# Analogue.net
KiCad netlist of a schematic drawn in Altium Designer
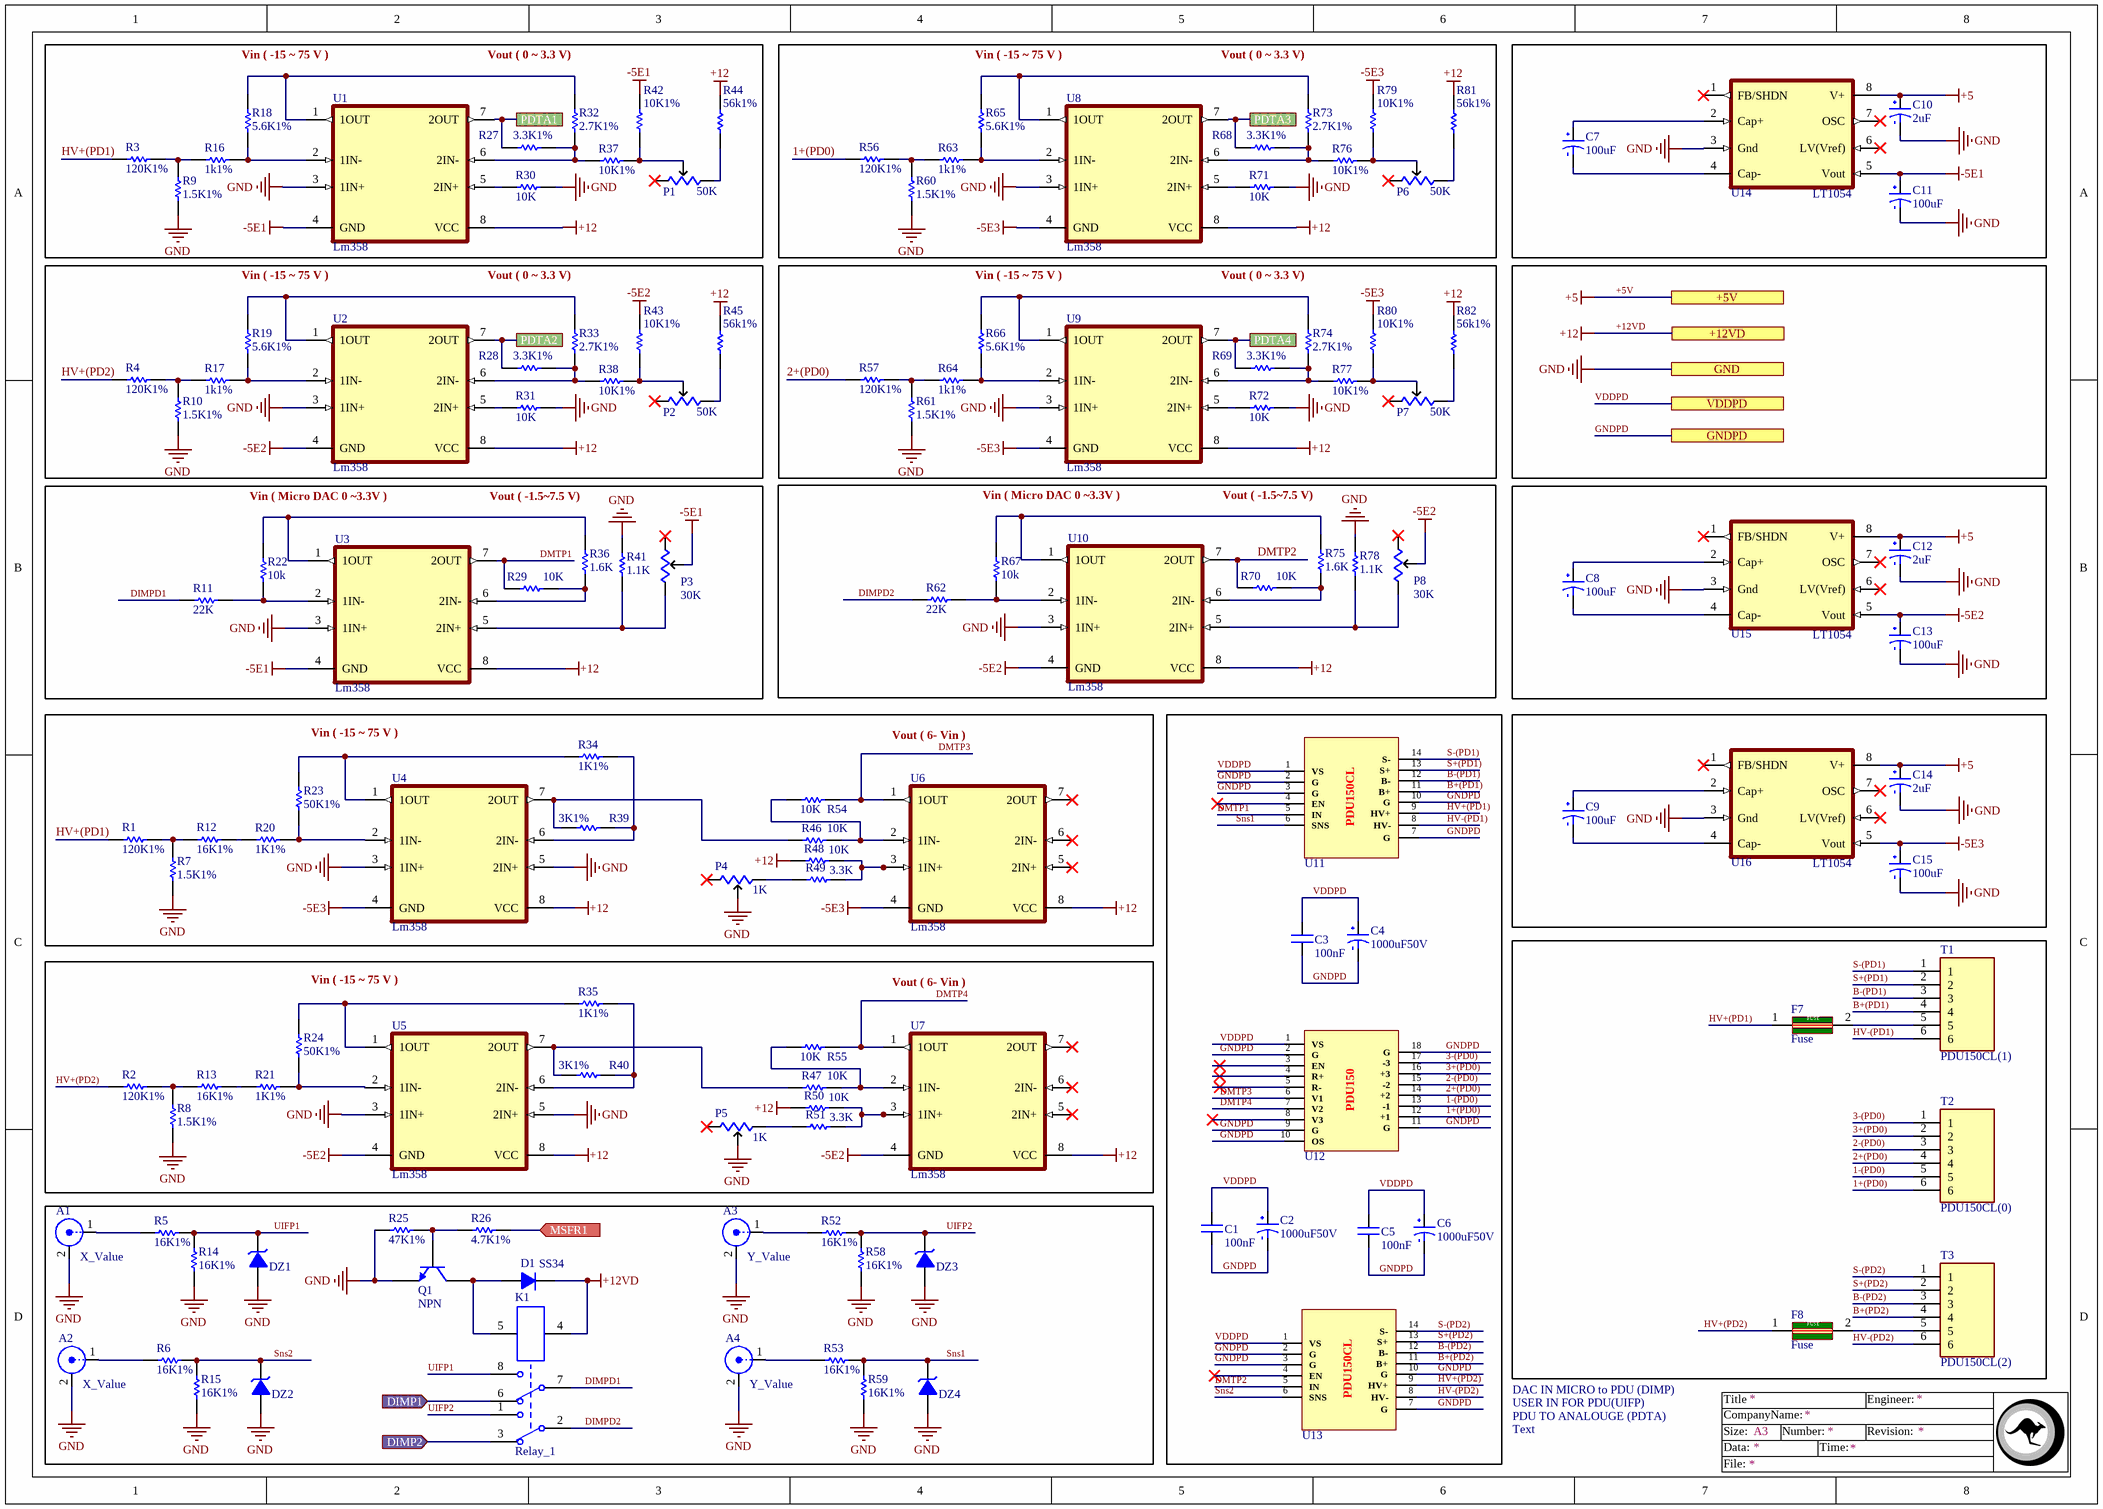
[diagram p0: Analogue.SchDoc]

(export (version "E")
  (design (tool "Eeschema 10.0.6"))
  (components
    (comp (ref "A1")
      (value "X_Value")
      (footprint "SMA - R")
      (description "Antena MLF")
      (libsource (lib "PMLIB2020-V3") (part "ANTENA"))
    )
    (comp (ref "A2")
      (value "X_Value")
      (footprint "SMA - R")
      (description "Antena MLF")
      (libsource (lib "PMLIB2020-V3") (part "ANTENA"))
    )
    (comp (ref "A3")
      (value "Y_Value")
      (footprint "SMA - R")
      (description "Antena MLF")
      (libsource (lib "PMLIB2020-V3") (part "ANTENA"))
    )
    (comp (ref "A4")
      (value "Y_Value")
      (footprint "SMA - R")
      (description "Antena MLF")
      (libsource (lib "PMLIB2020-V3") (part "ANTENA"))
    )
    (comp (ref "C1")
      (value "100nF")
      (footprint "Cap0805")
      (description "Surface mount Capacitor")
      (libsource (lib "PMLIB2020-V3") (part "Cap"))
    )
    (comp (ref "C2")
      (value "1000uF50V")
      (footprint "Cap_5mm")
      (description "Polarity")
      (libsource (lib "PMLIB2020-V3") (part "Cap_P"))
    )
    (comp (ref "C3")
      (value "100nF")
      (footprint "Cap0805")
      (description "Surface mount Capacitor")
      (libsource (lib "PMLIB2020-V3") (part "Cap"))
    )
    (comp (ref "C4")
      (value "1000uF50V")
      (footprint "Cap_5mm")
      (description "Polarity")
      (libsource (lib "PMLIB2020-V3") (part "Cap_P"))
    )
    (comp (ref "C5")
      (value "100nF")
      (footprint "Cap0805")
      (description "Surface mount Capacitor")
      (libsource (lib "PMLIB2020-V3") (part "Cap"))
    )
    (comp (ref "C6")
      (value "1000uF50V")
      (footprint "Cap_5mm")
      (description "Polarity")
      (libsource (lib "PMLIB2020-V3") (part "Cap_P"))
    )
    (comp (ref "C7")
      (value "100uF")
      (footprint "CAPMOL_D")
      (description "Polarity")
      (libsource (lib "PMLIB2020-V3") (part "Cap_P"))
    )
    (comp (ref "C8")
      (value "100uF")
      (footprint "CAPMOL_D")
      (description "Polarity")
      (libsource (lib "PMLIB2020-V3") (part "Cap_P"))
    )
    (comp (ref "C9")
      (value "100uF")
      (footprint "CAPMOL_D")
      (description "Polarity")
      (libsource (lib "PMLIB2020-V3") (part "Cap_P"))
    )
    (comp (ref "C10")
      (value "2uF")
      (footprint "CAPMOL_B")
      (description "Polarity")
      (libsource (lib "PMLIB2020-V3") (part "Cap_P"))
    )
    (comp (ref "C11")
      (value "100uF")
      (footprint "CAPMOL_D")
      (description "Polarity")
      (libsource (lib "PMLIB2020-V3") (part "Cap_P"))
    )
    (comp (ref "C12")
      (value "2uF")
      (footprint "CAPMOL_B")
      (description "Polarity")
      (libsource (lib "PMLIB2020-V3") (part "Cap_P"))
    )
    (comp (ref "C13")
      (value "100uF")
      (footprint "CAPMOL_D")
      (description "Polarity")
      (libsource (lib "PMLIB2020-V3") (part "Cap_P"))
    )
    (comp (ref "C14")
      (value "2uF")
      (footprint "CAPMOL_B")
      (description "Polarity")
      (libsource (lib "PMLIB2020-V3") (part "Cap_P"))
    )
    (comp (ref "C15")
      (value "100uF")
      (footprint "CAPMOL_D")
      (description "Polarity")
      (libsource (lib "PMLIB2020-V3") (part "Cap_P"))
    )
    (comp (ref "D1")
      (value "SS34")
      (footprint "Diod-1A-SMD")
      (description "Diode")
      (libsource (lib "PMLIB2020-V3") (part "Diode"))
    )
    (comp (ref "DZ1")
      (value "Diode Zener")
      (footprint "LL4148")
      (libsource (lib "PMLIB2020-V3") (part "Diode Zener"))
    )
    (comp (ref "DZ2")
      (value "Diode Zener")
      (footprint "LL4148")
      (libsource (lib "PMLIB2020-V3") (part "Diode Zener"))
    )
    (comp (ref "DZ3")
      (value "Diode Zener")
      (footprint "LL4148")
      (libsource (lib "PMLIB2020-V3") (part "Diode Zener"))
    )
    (comp (ref "DZ4")
      (value "Diode Zener")
      (footprint "LL4148")
      (libsource (lib "PMLIB2020-V3") (part "Diode Zener"))
    )
    (comp (ref "F7") (value "Fuse") (footprint "1206") (libsource (lib "PMLIB2020-V3") (part "Fuse")))
    (comp (ref "F8") (value "Fuse") (footprint "1206") (libsource (lib "PMLIB2020-V3") (part "Fuse")))
    (comp (ref "K1")
      (value "Relay_1")
      (footprint "Relay_1")
      (description "Relay")
      (libsource (lib "PMLIB2020-V3") (part "Relay_1"))
    )
    (comp (ref "P1")
      (value "50K")
      (footprint "Multi_tern")
      (description "Potentiometer")
      (libsource (lib "PMLIB2020-V3") (part "POT"))
    )
    (comp (ref "P2")
      (value "50K")
      (footprint "Multi_tern")
      (description "Potentiometer")
      (libsource (lib "PMLIB2020-V3") (part "POT"))
    )
    (comp (ref "P3")
      (value "30K")
      (footprint "Multi_tern")
      (description "Potentiometer")
      (libsource (lib "PMLIB2020-V3") (part "POT"))
    )
    (comp (ref "P4")
      (value "1K")
      (footprint "Multi_tern")
      (description "Potentiometer")
      (libsource (lib "PMLIB2020-V3") (part "POT"))
    )
    (comp (ref "P5")
      (value "1K")
      (footprint "Multi_tern")
      (description "Potentiometer")
      (libsource (lib "PMLIB2020-V3") (part "POT"))
    )
    (comp (ref "P6")
      (value "50K")
      (footprint "Multi_tern")
      (description "Potentiometer")
      (libsource (lib "PMLIB2020-V3") (part "POT"))
    )
    (comp (ref "P7")
      (value "50K")
      (footprint "Multi_tern")
      (description "Potentiometer")
      (libsource (lib "PMLIB2020-V3") (part "POT"))
    )
    (comp (ref "P8")
      (value "30K")
      (footprint "Multi_tern")
      (description "Potentiometer")
      (libsource (lib "PMLIB2020-V3") (part "POT"))
    )
    (comp (ref "Q1")
      (value "NPN")
      (footprint "SOT23_BEC_N")
      (description "NPN Bipolar Transistor")
      (fields (field (name "PUBLISHER") "Altium Limited"))
      (libsource (lib "PMLIB2020-V3") (part "NPN"))
    )
    (comp (ref "R1")
      (value "120K1%")
      (footprint "R0805")
      (description "30K")
      (libsource (lib "PMLIB2020-V3") (part "Resistor"))
    )
    (comp (ref "R2")
      (value "120K1%")
      (footprint "R0805")
      (description "30K")
      (libsource (lib "PMLIB2020-V3") (part "Resistor"))
    )
    (comp (ref "R3")
      (value "120K1%")
      (footprint "R0805")
      (description "30K")
      (libsource (lib "PMLIB2020-V3") (part "Resistor"))
    )
    (comp (ref "R4")
      (value "120K1%")
      (footprint "R0805")
      (description "30K")
      (libsource (lib "PMLIB2020-V3") (part "Resistor"))
    )
    (comp (ref "R5")
      (value "16K1%")
      (footprint "R0805")
      (description "30K")
      (libsource (lib "PMLIB2020-V3") (part "Resistor"))
    )
    (comp (ref "R6")
      (value "16K1%")
      (footprint "R0805")
      (description "30K")
      (libsource (lib "PMLIB2020-V3") (part "Resistor"))
    )
    (comp (ref "R7")
      (value "1.5K1%")
      (footprint "R0805")
      (description "30K")
      (libsource (lib "PMLIB2020-V3") (part "Resistor"))
    )
    (comp (ref "R8")
      (value "1.5K1%")
      (footprint "R0805")
      (description "30K")
      (libsource (lib "PMLIB2020-V3") (part "Resistor"))
    )
    (comp (ref "R9")
      (value "1.5K1%")
      (footprint "R0805")
      (description "30K")
      (libsource (lib "PMLIB2020-V3") (part "Resistor"))
    )
    (comp (ref "R10")
      (value "1.5K1%")
      (footprint "R0805")
      (description "30K")
      (libsource (lib "PMLIB2020-V3") (part "Resistor"))
    )
    (comp (ref "R11")
      (value "22K")
      (footprint "R0805")
      (description "30K")
      (libsource (lib "PMLIB2020-V3") (part "Resistor"))
    )
    (comp (ref "R12")
      (value "16K1%")
      (footprint "R0805")
      (description "30K")
      (libsource (lib "PMLIB2020-V3") (part "Resistor"))
    )
    (comp (ref "R13")
      (value "16K1%")
      (footprint "R0805")
      (description "30K")
      (libsource (lib "PMLIB2020-V3") (part "Resistor"))
    )
    (comp (ref "R14")
      (value "16K1%")
      (footprint "R0805")
      (description "30K")
      (libsource (lib "PMLIB2020-V3") (part "Resistor"))
    )
    (comp (ref "R15")
      (value "16K1%")
      (footprint "R0805")
      (description "30K")
      (libsource (lib "PMLIB2020-V3") (part "Resistor"))
    )
    (comp (ref "R16")
      (value "1k1%")
      (footprint "R0805")
      (description "30K")
      (libsource (lib "PMLIB2020-V3") (part "Resistor"))
    )
    (comp (ref "R17")
      (value "1k1%")
      (footprint "R0805")
      (description "30K")
      (libsource (lib "PMLIB2020-V3") (part "Resistor"))
    )
    (comp (ref "R18")
      (value "5.6K1%")
      (footprint "R0805")
      (description "Resistor")
      (libsource (lib "PMLIB2020-V3") (part "Resistor"))
    )
    (comp (ref "R19")
      (value "5.6K1%")
      (footprint "R0805")
      (description "Resistor")
      (libsource (lib "PMLIB2020-V3") (part "Resistor"))
    )
    (comp (ref "R20")
      (value "1K1%")
      (footprint "R0805")
      (description "30K")
      (libsource (lib "PMLIB2020-V3") (part "Resistor"))
    )
    (comp (ref "R21")
      (value "1K1%")
      (footprint "R0805")
      (description "30K")
      (libsource (lib "PMLIB2020-V3") (part "Resistor"))
    )
    (comp (ref "R22")
      (value "10k")
      (footprint "R0805")
      (description "Resistor")
      (libsource (lib "PMLIB2020-V3") (part "Resistor"))
    )
    (comp (ref "R23")
      (value "50K1%")
      (footprint "R0805")
      (description "Resistor")
      (libsource (lib "PMLIB2020-V3") (part "Resistor"))
    )
    (comp (ref "R24")
      (value "50K1%")
      (footprint "R0805")
      (description "Resistor")
      (libsource (lib "PMLIB2020-V3") (part "Resistor"))
    )
    (comp (ref "R25")
      (value "47K1%")
      (footprint "R0805")
      (description "30K")
      (libsource (lib "PMLIB2020-V3") (part "Resistor"))
    )
    (comp (ref "R26")
      (value "4.7K1%")
      (footprint "R0805")
      (description "30K")
      (libsource (lib "PMLIB2020-V3") (part "Resistor"))
    )
    (comp (ref "R27")
      (value "3.3K1%")
      (footprint "R0805")
      (description "Resistor")
      (libsource (lib "PMLIB2020-V3") (part "Resistor"))
    )
    (comp (ref "R28")
      (value "3.3K1%")
      (footprint "R0805")
      (description "Resistor")
      (libsource (lib "PMLIB2020-V3") (part "Resistor"))
    )
    (comp (ref "R29")
      (value "10K")
      (footprint "R0805")
      (description "Resistor")
      (libsource (lib "PMLIB2020-V3") (part "Resistor"))
    )
    (comp (ref "R30")
      (value "10K")
      (footprint "R0805")
      (description "Resistor")
      (libsource (lib "PMLIB2020-V3") (part "Resistor"))
    )
    (comp (ref "R31")
      (value "10K")
      (footprint "R0805")
      (description "Resistor")
      (libsource (lib "PMLIB2020-V3") (part "Resistor"))
    )
    (comp (ref "R32")
      (value "2.7K1%")
      (footprint "R0805")
      (description "Resistor")
      (libsource (lib "PMLIB2020-V3") (part "Resistor"))
    )
    (comp (ref "R33")
      (value "2.7K1%")
      (footprint "R0805")
      (description "Resistor")
      (libsource (lib "PMLIB2020-V3") (part "Resistor"))
    )
    (comp (ref "R34")
      (value "1K1%")
      (footprint "R0805")
      (description "Resistor")
      (libsource (lib "PMLIB2020-V3") (part "Resistor"))
    )
    (comp (ref "R35")
      (value "1K1%")
      (footprint "R0805")
      (description "Resistor")
      (libsource (lib "PMLIB2020-V3") (part "Resistor"))
    )
    (comp (ref "R36")
      (value "1.6K")
      (footprint "R0805")
      (description "Resistor")
      (libsource (lib "PMLIB2020-V3") (part "Resistor"))
    )
    (comp (ref "R37")
      (value "10K1%")
      (footprint "R0805")
      (description "Resistor")
      (libsource (lib "PMLIB2020-V3") (part "Resistor"))
    )
    (comp (ref "R38")
      (value "10K1%")
      (footprint "R0805")
      (description "Resistor")
      (libsource (lib "PMLIB2020-V3") (part "Resistor"))
    )
    (comp (ref "R39")
      (value "3K1%")
      (footprint "R0805")
      (description "Resistor")
      (libsource (lib "PMLIB2020-V3") (part "Resistor"))
    )
    (comp (ref "R40")
      (value "3K1%")
      (footprint "R0805")
      (description "Resistor")
      (libsource (lib "PMLIB2020-V3") (part "Resistor"))
    )
    (comp (ref "R41")
      (value "1.1K")
      (footprint "R0805")
      (description "Resistor")
      (libsource (lib "PMLIB2020-V3") (part "Resistor"))
    )
    (comp (ref "R42")
      (value "10K1%")
      (footprint "R0805")
      (description "Resistor")
      (libsource (lib "PMLIB2020-V3") (part "Resistor"))
    )
    (comp (ref "R43")
      (value "10K1%")
      (footprint "R0805")
      (description "Resistor")
      (libsource (lib "PMLIB2020-V3") (part "Resistor"))
    )
    (comp (ref "R44")
      (value "56k1%")
      (footprint "R0805")
      (description "Resistor")
      (libsource (lib "PMLIB2020-V3") (part "Resistor"))
    )
    (comp (ref "R45")
      (value "56k1%")
      (footprint "R0805")
      (description "Resistor")
      (libsource (lib "PMLIB2020-V3") (part "Resistor"))
    )
    (comp (ref "R46")
      (value "10K")
      (footprint "R0805")
      (description "Resistor")
      (libsource (lib "PMLIB2020-V3") (part "Resistor"))
    )
    (comp (ref "R47")
      (value "10K")
      (footprint "R0805")
      (description "Resistor")
      (libsource (lib "PMLIB2020-V3") (part "Resistor"))
    )
    (comp (ref "R48")
      (value "10K")
      (footprint "R0805")
      (description "Resistor")
      (libsource (lib "PMLIB2020-V3") (part "Resistor"))
    )
    (comp (ref "R49")
      (value "3.3K")
      (footprint "R0805")
      (description "Resistor")
      (libsource (lib "PMLIB2020-V3") (part "Resistor"))
    )
    (comp (ref "R50")
      (value "10K")
      (footprint "R0805")
      (description "Resistor")
      (libsource (lib "PMLIB2020-V3") (part "Resistor"))
    )
    (comp (ref "R51")
      (value "3.3K")
      (footprint "R0805")
      (description "Resistor")
      (libsource (lib "PMLIB2020-V3") (part "Resistor"))
    )
    (comp (ref "R52")
      (value "16K1%")
      (footprint "R0805")
      (description "30K")
      (libsource (lib "PMLIB2020-V3") (part "Resistor"))
    )
    (comp (ref "R53")
      (value "16K1%")
      (footprint "R0805")
      (description "30K")
      (libsource (lib "PMLIB2020-V3") (part "Resistor"))
    )
    (comp (ref "R54")
      (value "10K")
      (footprint "R0805")
      (description "Resistor")
      (libsource (lib "PMLIB2020-V3") (part "Resistor"))
    )
    (comp (ref "R55")
      (value "10K")
      (footprint "R0805")
      (description "Resistor")
      (libsource (lib "PMLIB2020-V3") (part "Resistor"))
    )
    (comp (ref "R56")
      (value "120K1%")
      (footprint "R0805")
      (description "30K")
      (libsource (lib "PMLIB2020-V3") (part "Resistor"))
    )
    (comp (ref "R57")
      (value "120K1%")
      (footprint "R0805")
      (description "30K")
      (libsource (lib "PMLIB2020-V3") (part "Resistor"))
    )
    (comp (ref "R58")
      (value "16K1%")
      (footprint "R0805")
      (description "30K")
      (libsource (lib "PMLIB2020-V3") (part "Resistor"))
    )
    (comp (ref "R59")
      (value "16K1%")
      (footprint "R0805")
      (description "30K")
      (libsource (lib "PMLIB2020-V3") (part "Resistor"))
    )
    (comp (ref "R60")
      (value "1.5K1%")
      (footprint "R0805")
      (description "30K")
      (libsource (lib "PMLIB2020-V3") (part "Resistor"))
    )
    (comp (ref "R61")
      (value "1.5K1%")
      (footprint "R0805")
      (description "30K")
      (libsource (lib "PMLIB2020-V3") (part "Resistor"))
    )
    (comp (ref "R62")
      (value "22K")
      (footprint "R0805")
      (description "30K")
      (libsource (lib "PMLIB2020-V3") (part "Resistor"))
    )
    (comp (ref "R63")
      (value "1k1%")
      (footprint "R0805")
      (description "30K")
      (libsource (lib "PMLIB2020-V3") (part "Resistor"))
    )
    (comp (ref "R64")
      (value "1k1%")
      (footprint "R0805")
      (description "30K")
      (libsource (lib "PMLIB2020-V3") (part "Resistor"))
    )
    (comp (ref "R65")
      (value "5.6K1%")
      (footprint "R0805")
      (description "Resistor")
      (libsource (lib "PMLIB2020-V3") (part "Resistor"))
    )
    (comp (ref "R66")
      (value "5.6K1%")
      (footprint "R0805")
      (description "Resistor")
      (libsource (lib "PMLIB2020-V3") (part "Resistor"))
    )
    (comp (ref "R67")
      (value "10k")
      (footprint "R0805")
      (description "Resistor")
      (libsource (lib "PMLIB2020-V3") (part "Resistor"))
    )
    (comp (ref "R68")
      (value "3.3K1%")
      (footprint "R0805")
      (description "Resistor")
      (libsource (lib "PMLIB2020-V3") (part "Resistor"))
    )
    (comp (ref "R69")
      (value "3.3K1%")
      (footprint "R0805")
      (description "Resistor")
      (libsource (lib "PMLIB2020-V3") (part "Resistor"))
    )
    (comp (ref "R70")
      (value "10K")
      (footprint "R0805")
      (description "Resistor")
      (libsource (lib "PMLIB2020-V3") (part "Resistor"))
    )
    (comp (ref "R71")
      (value "10K")
      (footprint "R0805")
      (description "Resistor")
      (libsource (lib "PMLIB2020-V3") (part "Resistor"))
    )
    (comp (ref "R72")
      (value "10K")
      (footprint "R0805")
      (description "Resistor")
      (libsource (lib "PMLIB2020-V3") (part "Resistor"))
    )
    (comp (ref "R73")
      (value "2.7K1%")
      (footprint "R0805")
      (description "Resistor")
      (libsource (lib "PMLIB2020-V3") (part "Resistor"))
    )
    (comp (ref "R74")
      (value "2.7K1%")
      (footprint "R0805")
      (description "Resistor")
      (libsource (lib "PMLIB2020-V3") (part "Resistor"))
    )
    (comp (ref "R75")
      (value "1.6K")
      (footprint "R0805")
      (description "Resistor")
      (libsource (lib "PMLIB2020-V3") (part "Resistor"))
    )
    (comp (ref "R76")
      (value "10K1%")
      (footprint "R0805")
      (description "Resistor")
      (libsource (lib "PMLIB2020-V3") (part "Resistor"))
    )
    (comp (ref "R77")
      (value "10K1%")
      (footprint "R0805")
      (description "Resistor")
      (libsource (lib "PMLIB2020-V3") (part "Resistor"))
    )
    (comp (ref "R78")
      (value "1.1K")
      (footprint "R0805")
      (description "Resistor")
      (libsource (lib "PMLIB2020-V3") (part "Resistor"))
    )
    (comp (ref "R79")
      (value "10K1%")
      (footprint "R0805")
      (description "Resistor")
      (libsource (lib "PMLIB2020-V3") (part "Resistor"))
    )
    (comp (ref "R80")
      (value "10K1%")
      (footprint "R0805")
      (description "Resistor")
      (libsource (lib "PMLIB2020-V3") (part "Resistor"))
    )
    (comp (ref "R81")
      (value "56k1%")
      (footprint "R0805")
      (description "Resistor")
      (libsource (lib "PMLIB2020-V3") (part "Resistor"))
    )
    (comp (ref "R82")
      (value "56k1%")
      (footprint "R0805")
      (description "Resistor")
      (libsource (lib "PMLIB2020-V3") (part "Resistor"))
    )
    (comp (ref "T1")
      (value "PDU150CL(1)")
      (footprint "SPOX6")
      (libsource (lib "PMLIB2020-V3") (part "SPOX 1*6"))
    )
    (comp (ref "T2")
      (value "PDU150CL(0)")
      (footprint "SPOX6")
      (libsource (lib "PMLIB2020-V3") (part "SPOX 1*6"))
    )
    (comp (ref "T3")
      (value "PDU150CL(2)")
      (footprint "SPOX6")
      (libsource (lib "PMLIB2020-V3") (part "SPOX 1*6"))
    )
    (comp (ref "U1")
      (value "Lm358")
      (footprint "SOIC127P600X175-8N")
      (libsource (lib "PMLIB2020-V3") (part "Lm358"))
    )
    (comp (ref "U2")
      (value "Lm358")
      (footprint "SOIC127P600X175-8N")
      (libsource (lib "PMLIB2020-V3") (part "Lm358"))
    )
    (comp (ref "U3")
      (value "Lm358")
      (footprint "SOIC127P600X175-8N")
      (libsource (lib "PMLIB2020-V3") (part "Lm358"))
    )
    (comp (ref "U4")
      (value "Lm358")
      (footprint "SOIC127P600X175-8N")
      (libsource (lib "PMLIB2020-V3") (part "Lm358"))
    )
    (comp (ref "U5")
      (value "Lm358")
      (footprint "SOIC127P600X175-8N")
      (libsource (lib "PMLIB2020-V3") (part "Lm358"))
    )
    (comp (ref "U6")
      (value "Lm358")
      (footprint "SOIC127P600X175-8N")
      (libsource (lib "PMLIB2020-V3") (part "Lm358"))
    )
    (comp (ref "U7")
      (value "Lm358")
      (footprint "SOIC127P600X175-8N")
      (libsource (lib "PMLIB2020-V3") (part "Lm358"))
    )
    (comp (ref "U8")
      (value "Lm358")
      (footprint "SOIC127P600X175-8N")
      (libsource (lib "PMLIB2020-V3") (part "Lm358"))
    )
    (comp (ref "U9")
      (value "Lm358")
      (footprint "SOIC127P600X175-8N")
      (libsource (lib "PMLIB2020-V3") (part "Lm358"))
    )
    (comp (ref "U10")
      (value "Lm358")
      (footprint "SOIC127P600X175-8N")
      (libsource (lib "PMLIB2020-V3") (part "Lm358"))
    )
    (comp (ref "U11")
      (value "PDU150CL")
      (footprint "PDU150CL")
      (libsource (lib "PMLIB2020-V3") (part "PDU150CL"))
    )
    (comp (ref "U12") (value "PDU150") (footprint "PDU150") (libsource (lib "PMLIB2020-V3") (part "PDU150")))
    (comp (ref "U13")
      (value "PDU150CL")
      (footprint "PDU150CL")
      (libsource (lib "PMLIB2020-V3") (part "PDU150CL"))
    )
    (comp (ref "U14")
      (value "LT1054")
      (footprint "SOIC127P600X175-8N")
      (libsource (lib "PMLIB2020-V3") (part "LMC7660"))
    )
    (comp (ref "U15")
      (value "LT1054")
      (footprint "SOIC127P600X175-8N")
      (libsource (lib "PMLIB2020-V3") (part "LMC7660"))
    )
    (comp (ref "U16")
      (value "LT1054")
      (footprint "SOIC127P600X175-8N")
      (libsource (lib "PMLIB2020-V3") (part "LMC7660"))
    )
  )
  (nets
    (net (code "1") (name "+5") (class "Default")
      (node (ref "C10") (pin "2") (pinfunction "2_2") (pintype "passive"))
      (node (ref "C12") (pin "2") (pinfunction "2_2") (pintype "passive"))
      (node (ref "C14") (pin "2") (pinfunction "2_2") (pintype "passive"))
      (node (ref "U14") (pin "8") (pinfunction "V+_8") (pintype "power_in"))
      (node (ref "U15") (pin "8") (pinfunction "V+_8") (pintype "power_in"))
      (node (ref "U16") (pin "8") (pinfunction "V+_8") (pintype "power_in"))
    )
    (net (code "2") (name "+12") (class "Default")
      (node (ref "D1") (pin "K") (pinfunction "K_K") (pintype "passive"))
      (node (ref "K1") (pin "4") (pinfunction "4_4") (pintype "passive"))
      (node (ref "R44") (pin "1") (pinfunction "1_1") (pintype "passive"))
      (node (ref "R45") (pin "1") (pinfunction "1_1") (pintype "passive"))
      (node (ref "R48") (pin "1") (pinfunction "1_1") (pintype "passive"))
      (node (ref "R50") (pin "1") (pinfunction "1_1") (pintype "passive"))
      (node (ref "R81") (pin "1") (pinfunction "1_1") (pintype "passive"))
      (node (ref "R82") (pin "1") (pinfunction "1_1") (pintype "passive"))
      (node (ref "U1") (pin "8") (pinfunction "VCC_8") (pintype "power_in"))
      (node (ref "U10") (pin "8") (pinfunction "VCC_8") (pintype "power_in"))
      (node (ref "U2") (pin "8") (pinfunction "VCC_8") (pintype "power_in"))
      (node (ref "U3") (pin "8") (pinfunction "VCC_8") (pintype "power_in"))
      (node (ref "U4") (pin "8") (pinfunction "VCC_8") (pintype "power_in"))
      (node (ref "U5") (pin "8") (pinfunction "VCC_8") (pintype "power_in"))
      (node (ref "U6") (pin "8") (pinfunction "VCC_8") (pintype "power_in"))
      (node (ref "U7") (pin "8") (pinfunction "VCC_8") (pintype "power_in"))
      (node (ref "U8") (pin "8") (pinfunction "VCC_8") (pintype "power_in"))
      (node (ref "U9") (pin "8") (pinfunction "VCC_8") (pintype "power_in"))
    )
    (net (code "3") (name "-5E1") (class "Default")
      (node (ref "C11") (pin "2") (pinfunction "2_2") (pintype "passive"))
      (node (ref "P3") (pin "2") (pinfunction "2_2") (pintype "passive"))
      (node (ref "R42") (pin "1") (pinfunction "1_1") (pintype "passive"))
      (node (ref "U1") (pin "4") (pinfunction "GND_4") (pintype "power_in"))
      (node (ref "U14") (pin "5") (pinfunction "Vout_5") (pintype "input"))
      (node (ref "U3") (pin "4") (pinfunction "GND_4") (pintype "power_in"))
    )
    (net (code "4") (name "-5E2") (class "Default")
      (node (ref "C13") (pin "2") (pinfunction "2_2") (pintype "passive"))
      (node (ref "P8") (pin "2") (pinfunction "2_2") (pintype "passive"))
      (node (ref "R43") (pin "1") (pinfunction "1_1") (pintype "passive"))
      (node (ref "U10") (pin "4") (pinfunction "GND_4") (pintype "power_in"))
      (node (ref "U15") (pin "5") (pinfunction "Vout_5") (pintype "input"))
      (node (ref "U2") (pin "4") (pinfunction "GND_4") (pintype "power_in"))
      (node (ref "U5") (pin "4") (pinfunction "GND_4") (pintype "power_in"))
      (node (ref "U7") (pin "4") (pinfunction "GND_4") (pintype "power_in"))
    )
    (net (code "5") (name "-5E3") (class "Default")
      (node (ref "C15") (pin "2") (pinfunction "2_2") (pintype "passive"))
      (node (ref "R79") (pin "1") (pinfunction "1_1") (pintype "passive"))
      (node (ref "R80") (pin "1") (pinfunction "1_1") (pintype "passive"))
      (node (ref "U16") (pin "5") (pinfunction "Vout_5") (pintype "input"))
      (node (ref "U4") (pin "4") (pinfunction "GND_4") (pintype "power_in"))
      (node (ref "U6") (pin "4") (pinfunction "GND_4") (pintype "power_in"))
      (node (ref "U8") (pin "4") (pinfunction "GND_4") (pintype "power_in"))
      (node (ref "U9") (pin "4") (pinfunction "GND_4") (pintype "power_in"))
    )
    (net (code "6") (name "/1+(PD0)") (class "Default")
      (node (ref "R56") (pin "2") (pinfunction "2_2") (pintype "passive"))
      (node (ref "T2") (pin "6") (pinfunction "6_6") (pintype "passive"))
      (node (ref "U12") (pin "12") (pinfunction "+1_12") (pintype "passive"))
    )
    (net (code "7") (name "/1-(PD0)") (class "Default")
      (node (ref "T2") (pin "5") (pinfunction "5_5") (pintype "passive"))
      (node (ref "U12") (pin "13") (pinfunction "-1_13") (pintype "passive"))
    )
    (net (code "8") (name "/2+(PD0)") (class "Default")
      (node (ref "R57") (pin "2") (pinfunction "2_2") (pintype "passive"))
      (node (ref "T2") (pin "4") (pinfunction "4_4") (pintype "passive"))
      (node (ref "U12") (pin "14") (pinfunction "+2_14") (pintype "passive"))
    )
    (net (code "9") (name "/2-(PD0)") (class "Default")
      (node (ref "T2") (pin "3") (pinfunction "3_3") (pintype "passive"))
      (node (ref "U12") (pin "15") (pinfunction "-2_15") (pintype "passive"))
    )
    (net (code "10") (name "/3+(PD0)") (class "Default")
      (node (ref "T2") (pin "2") (pinfunction "2_2") (pintype "passive"))
      (node (ref "U12") (pin "16") (pinfunction "+3_16") (pintype "passive"))
    )
    (net (code "11") (name "/3-(PD0)") (class "Default")
      (node (ref "T2") (pin "1") (pinfunction "1_1") (pintype "passive"))
      (node (ref "U12") (pin "17") (pinfunction "-3_17") (pintype "passive"))
    )
    (net (code "12") (name "/B+(PD1)") (class "Default")
      (node (ref "T1") (pin "4") (pinfunction "4_4") (pintype "passive"))
      (node (ref "U11") (pin "11") (pinfunction "B+_11") (pintype "passive"))
    )
    (net (code "13") (name "/B+(PD2)") (class "Default")
      (node (ref "T3") (pin "4") (pinfunction "4_4") (pintype "passive"))
      (node (ref "U13") (pin "11") (pinfunction "B+_11") (pintype "passive"))
    )
    (net (code "14") (name "/B-(PD1)") (class "Default")
      (node (ref "T1") (pin "3") (pinfunction "3_3") (pintype "passive"))
      (node (ref "U11") (pin "12") (pinfunction "B-_12") (pintype "passive"))
    )
    (net (code "15") (name "/B-(PD2)") (class "Default")
      (node (ref "T3") (pin "3") (pinfunction "3_3") (pintype "passive"))
      (node (ref "U13") (pin "12") (pinfunction "B-_12") (pintype "passive"))
    )
    (net (code "16") (name "/DIMP1") (class "Default")
      (node (ref "K1") (pin "6") (pinfunction "6_6") (pintype "passive"))
    )
    (net (code "17") (name "/DIMP2") (class "Default")
      (node (ref "K1") (pin "3") (pinfunction "3_3") (pintype "passive"))
    )
    (net (code "18") (name "/DIMPD1") (class "Default")
      (node (ref "K1") (pin "7") (pinfunction "7_7") (pintype "passive"))
      (node (ref "R11") (pin "1") (pinfunction "1_1") (pintype "passive"))
    )
    (net (code "19") (name "/DIMPD2") (class "Default")
      (node (ref "K1") (pin "2") (pinfunction "2_2") (pintype "passive"))
      (node (ref "R62") (pin "1") (pinfunction "1_1") (pintype "passive"))
    )
    (net (code "20") (name "/DMTP1") (class "Default")
      (node (ref "R29") (pin "1") (pinfunction "1_1") (pintype "passive"))
      (node (ref "U11") (pin "5") (pinfunction "IN_5") (pintype "passive"))
      (node (ref "U3") (pin "7") (pinfunction "2OUT_7") (pintype "output"))
    )
    (net (code "21") (name "/DMTP2") (class "Default")
      (node (ref "R70") (pin "1") (pinfunction "1_1") (pintype "passive"))
      (node (ref "U10") (pin "7") (pinfunction "2OUT_7") (pintype "output"))
      (node (ref "U13") (pin "5") (pinfunction "IN_5") (pintype "passive"))
    )
    (net (code "22") (name "/DMTP3") (class "Default")
      (node (ref "R54") (pin "2") (pinfunction "2_2") (pintype "passive"))
      (node (ref "U12") (pin "6") (pinfunction "V1_6") (pintype "passive"))
      (node (ref "U6") (pin "1") (pinfunction "1OUT_1") (pintype "output"))
    )
    (net (code "23") (name "/DMTP4") (class "Default")
      (node (ref "R55") (pin "2") (pinfunction "2_2") (pintype "passive"))
      (node (ref "U12") (pin "7") (pinfunction "V2_7") (pintype "passive"))
      (node (ref "U7") (pin "1") (pinfunction "1OUT_1") (pintype "output"))
    )
    (net (code "24") (name "/GNDPD") (class "Default")
      (node (ref "C1") (pin "1") (pinfunction "1_1") (pintype "passive"))
      (node (ref "C2") (pin "1") (pinfunction "1_1") (pintype "passive"))
      (node (ref "C3") (pin "1") (pinfunction "1_1") (pintype "passive"))
      (node (ref "C4") (pin "1") (pinfunction "1_1") (pintype "passive"))
      (node (ref "C5") (pin "1") (pinfunction "1_1") (pintype "passive"))
      (node (ref "C6") (pin "1") (pinfunction "1_1") (pintype "passive"))
      (node (ref "U11") (pin "10") (pinfunction "G_10") (pintype "passive"))
      (node (ref "U11") (pin "2") (pinfunction "G_2") (pintype "passive"))
      (node (ref "U11") (pin "3") (pinfunction "G_3") (pintype "passive"))
      (node (ref "U11") (pin "7") (pinfunction "G_7") (pintype "passive"))
      (node (ref "U12") (pin "10") (pinfunction "OS_10") (pintype "passive"))
      (node (ref "U12") (pin "11") (pinfunction "G_11") (pintype "passive"))
      (node (ref "U12") (pin "18") (pinfunction "G_18") (pintype "passive"))
      (node (ref "U12") (pin "2") (pinfunction "G_2") (pintype "passive"))
      (node (ref "U12") (pin "9") (pinfunction "G_9") (pintype "passive"))
      (node (ref "U13") (pin "10") (pinfunction "G_10") (pintype "passive"))
      (node (ref "U13") (pin "2") (pinfunction "G_2") (pintype "passive"))
      (node (ref "U13") (pin "3") (pinfunction "G_3") (pintype "passive"))
      (node (ref "U13") (pin "7") (pinfunction "G_7") (pintype "passive"))
    )
    (net (code "25") (name "/HV+(PD1)") (class "Default")
      (node (ref "F7") (pin "1") (pinfunction "IN_1") (pintype "passive"))
      (node (ref "R1") (pin "1") (pinfunction "1_1") (pintype "passive"))
      (node (ref "R3") (pin "2") (pinfunction "2_2") (pintype "passive"))
      (node (ref "U11") (pin "9") (pinfunction "HV+_9") (pintype "passive"))
    )
    (net (code "26") (name "/HV+(PD2)") (class "Default")
      (node (ref "F8") (pin "1") (pinfunction "IN_1") (pintype "passive"))
      (node (ref "R2") (pin "1") (pinfunction "1_1") (pintype "passive"))
      (node (ref "R4") (pin "2") (pinfunction "2_2") (pintype "passive"))
      (node (ref "U13") (pin "9") (pinfunction "HV+_9") (pintype "passive"))
    )
    (net (code "27") (name "/HV-(PD1)") (class "Default")
      (node (ref "T1") (pin "6") (pinfunction "6_6") (pintype "passive"))
      (node (ref "U11") (pin "8") (pinfunction "HV-_8") (pintype "passive"))
    )
    (net (code "28") (name "/HV-(PD2)") (class "Default")
      (node (ref "T3") (pin "6") (pinfunction "6_6") (pintype "passive"))
      (node (ref "U13") (pin "8") (pinfunction "HV-_8") (pintype "passive"))
    )
    (net (code "29") (name "/MSFR1") (class "Default")
      (node (ref "R26") (pin "1") (pinfunction "1_1") (pintype "passive"))
    )
    (net (code "30") (name "/PDTA1") (class "Default")
      (node (ref "R27") (pin "1") (pinfunction "1_1") (pintype "passive"))
      (node (ref "U1") (pin "7") (pinfunction "2OUT_7") (pintype "output"))
    )
    (net (code "31") (name "/PDTA2") (class "Default")
      (node (ref "R28") (pin "1") (pinfunction "1_1") (pintype "passive"))
      (node (ref "U2") (pin "7") (pinfunction "2OUT_7") (pintype "output"))
    )
    (net (code "32") (name "/PDTA3") (class "Default")
      (node (ref "R68") (pin "1") (pinfunction "1_1") (pintype "passive"))
      (node (ref "U8") (pin "7") (pinfunction "2OUT_7") (pintype "output"))
    )
    (net (code "33") (name "/PDTA4") (class "Default")
      (node (ref "R69") (pin "1") (pinfunction "1_1") (pintype "passive"))
      (node (ref "U9") (pin "7") (pinfunction "2OUT_7") (pintype "output"))
    )
    (net (code "34") (name "/S+(PD1)") (class "Default")
      (node (ref "T1") (pin "2") (pinfunction "2_2") (pintype "passive"))
      (node (ref "U11") (pin "13") (pinfunction "S+_13") (pintype "passive"))
    )
    (net (code "35") (name "/S+(PD2)") (class "Default")
      (node (ref "T3") (pin "2") (pinfunction "2_2") (pintype "passive"))
      (node (ref "U13") (pin "13") (pinfunction "S+_13") (pintype "passive"))
    )
    (net (code "36") (name "/S-(PD1)") (class "Default")
      (node (ref "T1") (pin "1") (pinfunction "1_1") (pintype "passive"))
      (node (ref "U11") (pin "14") (pinfunction "S-_14") (pintype "passive"))
    )
    (net (code "37") (name "/S-(PD2)") (class "Default")
      (node (ref "T3") (pin "1") (pinfunction "1_1") (pintype "passive"))
      (node (ref "U13") (pin "14") (pinfunction "S-_14") (pintype "passive"))
    )
    (net (code "38") (name "/Sns1") (class "Default")
      (node (ref "DZ4") (pin "K") (pinfunction "K_K") (pintype "passive"))
      (node (ref "R53") (pin "2") (pinfunction "2_2") (pintype "passive"))
      (node (ref "R59") (pin "2") (pinfunction "2_2") (pintype "passive"))
      (node (ref "U11") (pin "6") (pinfunction "SNS_6") (pintype "passive"))
    )
    (net (code "39") (name "/Sns2") (class "Default")
      (node (ref "DZ2") (pin "K") (pinfunction "K_K") (pintype "passive"))
      (node (ref "R15") (pin "2") (pinfunction "2_2") (pintype "passive"))
      (node (ref "R6") (pin "2") (pinfunction "2_2") (pintype "passive"))
      (node (ref "U13") (pin "6") (pinfunction "SNS_6") (pintype "passive"))
    )
    (net (code "40") (name "/UIFP1") (class "Default")
      (node (ref "DZ1") (pin "K") (pinfunction "K_K") (pintype "passive"))
      (node (ref "K1") (pin "8") (pinfunction "8_8") (pintype "passive"))
      (node (ref "R14") (pin "2") (pinfunction "2_2") (pintype "passive"))
      (node (ref "R5") (pin "2") (pinfunction "2_2") (pintype "passive"))
    )
    (net (code "41") (name "/UIFP2") (class "Default")
      (node (ref "DZ3") (pin "K") (pinfunction "K_K") (pintype "passive"))
      (node (ref "K1") (pin "1") (pinfunction "1_1") (pintype "passive"))
      (node (ref "R52") (pin "2") (pinfunction "2_2") (pintype "passive"))
      (node (ref "R58") (pin "2") (pinfunction "2_2") (pintype "passive"))
    )
    (net (code "42") (name "/VDDPD") (class "Default")
      (node (ref "C1") (pin "2") (pinfunction "2_2") (pintype "passive"))
      (node (ref "C2") (pin "2") (pinfunction "2_2") (pintype "passive"))
      (node (ref "C3") (pin "2") (pinfunction "2_2") (pintype "passive"))
      (node (ref "C4") (pin "2") (pinfunction "2_2") (pintype "passive"))
      (node (ref "C5") (pin "2") (pinfunction "2_2") (pintype "passive"))
      (node (ref "C6") (pin "2") (pinfunction "2_2") (pintype "passive"))
      (node (ref "U11") (pin "1") (pinfunction "VS_1") (pintype "passive"))
      (node (ref "U12") (pin "1") (pinfunction "VS_1") (pintype "passive"))
      (node (ref "U13") (pin "1") (pinfunction "VS_1") (pintype "passive"))
    )
    (net (code "43") (name "GND") (class "Default")
      (node (ref "A1") (pin "2") (pinfunction "Y_2") (pintype "passive"))
      (node (ref "A2") (pin "2") (pinfunction "Y_2") (pintype "passive"))
      (node (ref "A3") (pin "2") (pinfunction "Y_2") (pintype "passive"))
      (node (ref "A4") (pin "2") (pinfunction "Y_2") (pintype "passive"))
      (node (ref "C10") (pin "1") (pinfunction "1_1") (pintype "passive"))
      (node (ref "C11") (pin "1") (pinfunction "1_1") (pintype "passive"))
      (node (ref "C12") (pin "1") (pinfunction "1_1") (pintype "passive"))
      (node (ref "C13") (pin "1") (pinfunction "1_1") (pintype "passive"))
      (node (ref "C14") (pin "1") (pinfunction "1_1") (pintype "passive"))
      (node (ref "C15") (pin "1") (pinfunction "1_1") (pintype "passive"))
      (node (ref "DZ1") (pin "A") (pinfunction "A_A") (pintype "passive"))
      (node (ref "DZ2") (pin "A") (pinfunction "A_A") (pintype "passive"))
      (node (ref "DZ3") (pin "A") (pinfunction "A_A") (pintype "passive"))
      (node (ref "DZ4") (pin "A") (pinfunction "A_A") (pintype "passive"))
      (node (ref "P4") (pin "2") (pinfunction "2_2") (pintype "passive"))
      (node (ref "P5") (pin "2") (pinfunction "2_2") (pintype "passive"))
      (node (ref "Q1") (pin "2") (pinfunction "E_2") (pintype "passive"))
      (node (ref "R10") (pin "1") (pinfunction "1_1") (pintype "passive"))
      (node (ref "R14") (pin "1") (pinfunction "1_1") (pintype "passive"))
      (node (ref "R15") (pin "1") (pinfunction "1_1") (pintype "passive"))
      (node (ref "R25") (pin "2") (pinfunction "2_2") (pintype "passive"))
      (node (ref "R30") (pin "1") (pinfunction "1_1") (pintype "passive"))
      (node (ref "R31") (pin "1") (pinfunction "1_1") (pintype "passive"))
      (node (ref "R41") (pin "1") (pinfunction "1_1") (pintype "passive"))
      (node (ref "R58") (pin "1") (pinfunction "1_1") (pintype "passive"))
      (node (ref "R59") (pin "1") (pinfunction "1_1") (pintype "passive"))
      (node (ref "R60") (pin "1") (pinfunction "1_1") (pintype "passive"))
      (node (ref "R61") (pin "1") (pinfunction "1_1") (pintype "passive"))
      (node (ref "R7") (pin "1") (pinfunction "1_1") (pintype "passive"))
      (node (ref "R71") (pin "1") (pinfunction "1_1") (pintype "passive"))
      (node (ref "R72") (pin "1") (pinfunction "1_1") (pintype "passive"))
      (node (ref "R78") (pin "1") (pinfunction "1_1") (pintype "passive"))
      (node (ref "R8") (pin "1") (pinfunction "1_1") (pintype "passive"))
      (node (ref "R9") (pin "1") (pinfunction "1_1") (pintype "passive"))
      (node (ref "U1") (pin "3") (pinfunction "1IN+_3") (pintype "input"))
      (node (ref "U10") (pin "3") (pinfunction "1IN+_3") (pintype "input"))
      (node (ref "U14") (pin "3") (pinfunction "Gnd_3") (pintype "input"))
      (node (ref "U15") (pin "3") (pinfunction "Gnd_3") (pintype "input"))
      (node (ref "U16") (pin "3") (pinfunction "Gnd_3") (pintype "input"))
      (node (ref "U2") (pin "3") (pinfunction "1IN+_3") (pintype "input"))
      (node (ref "U3") (pin "3") (pinfunction "1IN+_3") (pintype "input"))
      (node (ref "U4") (pin "3") (pinfunction "1IN+_3") (pintype "input"))
      (node (ref "U4") (pin "5") (pinfunction "2IN+_5") (pintype "input"))
      (node (ref "U5") (pin "3") (pinfunction "1IN+_3") (pintype "input"))
      (node (ref "U5") (pin "5") (pinfunction "2IN+_5") (pintype "input"))
      (node (ref "U8") (pin "3") (pinfunction "1IN+_3") (pintype "input"))
      (node (ref "U9") (pin "3") (pinfunction "1IN+_3") (pintype "input"))
    )
    (net (code "44") (name "Net-(A1-X)") (class "Default")
      (node (ref "A1") (pin "1") (pinfunction "X_1") (pintype "passive"))
      (node (ref "R5") (pin "1") (pinfunction "1_1") (pintype "passive"))
    )
    (net (code "45") (name "Net-(A2-X)") (class "Default")
      (node (ref "A2") (pin "1") (pinfunction "X_1") (pintype "passive"))
      (node (ref "R6") (pin "1") (pinfunction "1_1") (pintype "passive"))
    )
    (net (code "46") (name "Net-(A3-X)") (class "Default")
      (node (ref "A3") (pin "1") (pinfunction "X_1") (pintype "passive"))
      (node (ref "R52") (pin "1") (pinfunction "1_1") (pintype "passive"))
    )
    (net (code "47") (name "Net-(A4-X)") (class "Default")
      (node (ref "A4") (pin "1") (pinfunction "X_1") (pintype "passive"))
      (node (ref "R53") (pin "1") (pinfunction "1_1") (pintype "passive"))
    )
    (net (code "48") (name "Net-(F7-OUT)") (class "Default")
      (node (ref "F7") (pin "2") (pinfunction "OUT_2") (pintype "passive"))
      (node (ref "T1") (pin "5") (pinfunction "5_5") (pintype "passive"))
    )
    (net (code "49") (name "Net-(F8-OUT)") (class "Default")
      (node (ref "F8") (pin "2") (pinfunction "OUT_2") (pintype "passive"))
      (node (ref "T3") (pin "5") (pinfunction "5_5") (pintype "passive"))
    )
    (net (code "50") (name "Net-(P1-Pad2)") (class "Default")
      (node (ref "P1") (pin "2") (pinfunction "2_2") (pintype "passive"))
      (node (ref "R37") (pin "1") (pinfunction "1_1") (pintype "passive"))
      (node (ref "R42") (pin "2") (pinfunction "2_2") (pintype "passive"))
    )
    (net (code "51") (name "Net-(P1-Pad3)") (class "Default")
      (node (ref "P1") (pin "3") (pinfunction "3_3") (pintype "passive"))
      (node (ref "R44") (pin "2") (pinfunction "2_2") (pintype "passive"))
    )
    (net (code "52") (name "Net-(P2-Pad2)") (class "Default")
      (node (ref "P2") (pin "2") (pinfunction "2_2") (pintype "passive"))
      (node (ref "R38") (pin "1") (pinfunction "1_1") (pintype "passive"))
      (node (ref "R43") (pin "2") (pinfunction "2_2") (pintype "passive"))
    )
    (net (code "53") (name "Net-(P2-Pad3)") (class "Default")
      (node (ref "P2") (pin "3") (pinfunction "3_3") (pintype "passive"))
      (node (ref "R45") (pin "2") (pinfunction "2_2") (pintype "passive"))
    )
    (net (code "54") (name "Net-(P4-Pad1)") (class "Default")
      (node (ref "P4") (pin "1") (pinfunction "1_1") (pintype "passive"))
      (node (ref "R49") (pin "1") (pinfunction "1_1") (pintype "passive"))
    )
    (net (code "55") (name "Net-(P5-Pad1)") (class "Default")
      (node (ref "P5") (pin "1") (pinfunction "1_1") (pintype "passive"))
      (node (ref "R51") (pin "1") (pinfunction "1_1") (pintype "passive"))
    )
    (net (code "56") (name "Net-(P6-Pad2)") (class "Default")
      (node (ref "P6") (pin "2") (pinfunction "2_2") (pintype "passive"))
      (node (ref "R76") (pin "1") (pinfunction "1_1") (pintype "passive"))
      (node (ref "R79") (pin "2") (pinfunction "2_2") (pintype "passive"))
    )
    (net (code "57") (name "Net-(P6-Pad3)") (class "Default")
      (node (ref "P6") (pin "3") (pinfunction "3_3") (pintype "passive"))
      (node (ref "R81") (pin "2") (pinfunction "2_2") (pintype "passive"))
    )
    (net (code "58") (name "Net-(P7-Pad2)") (class "Default")
      (node (ref "P7") (pin "2") (pinfunction "2_2") (pintype "passive"))
      (node (ref "R77") (pin "1") (pinfunction "1_1") (pintype "passive"))
      (node (ref "R80") (pin "2") (pinfunction "2_2") (pintype "passive"))
    )
    (net (code "59") (name "Net-(P7-Pad3)") (class "Default")
      (node (ref "P7") (pin "3") (pinfunction "3_3") (pintype "passive"))
      (node (ref "R82") (pin "2") (pinfunction "2_2") (pintype "passive"))
    )
    (net (code "60") (name "Net-(Q1-B)") (class "Default")
      (node (ref "Q1") (pin "1") (pinfunction "B_1") (pintype "passive"))
      (node (ref "R25") (pin "1") (pinfunction "1_1") (pintype "passive"))
      (node (ref "R26") (pin "2") (pinfunction "2_2") (pintype "passive"))
    )
    (net (code "61") (name "Net-(Q1-C)") (class "Default")
      (node (ref "D1") (pin "A") (pinfunction "A_A") (pintype "passive"))
      (node (ref "K1") (pin "5") (pinfunction "5_5") (pintype "passive"))
      (node (ref "Q1") (pin "3") (pinfunction "C_3") (pintype "passive"))
    )
    (net (code "62") (name "Net-(R1-Pad2)") (class "Default")
      (node (ref "R1") (pin "2") (pinfunction "2_2") (pintype "passive"))
      (node (ref "R12") (pin "1") (pinfunction "1_1") (pintype "passive"))
      (node (ref "R7") (pin "2") (pinfunction "2_2") (pintype "passive"))
    )
    (net (code "63") (name "Net-(R10-Pad2)") (class "Default")
      (node (ref "R10") (pin "2") (pinfunction "2_2") (pintype "passive"))
      (node (ref "R17") (pin "1") (pinfunction "1_1") (pintype "passive"))
      (node (ref "R4") (pin "1") (pinfunction "1_1") (pintype "passive"))
    )
    (net (code "64") (name "Net-(R12-Pad2)") (class "Default")
      (node (ref "R12") (pin "2") (pinfunction "2_2") (pintype "passive"))
      (node (ref "R20") (pin "1") (pinfunction "1_1") (pintype "passive"))
    )
    (net (code "65") (name "Net-(R13-Pad1)") (class "Default")
      (node (ref "R13") (pin "1") (pinfunction "1_1") (pintype "passive"))
      (node (ref "R2") (pin "2") (pinfunction "2_2") (pintype "passive"))
      (node (ref "R8") (pin "2") (pinfunction "2_2") (pintype "passive"))
    )
    (net (code "66") (name "Net-(R13-Pad2)") (class "Default")
      (node (ref "R13") (pin "2") (pinfunction "2_2") (pintype "passive"))
      (node (ref "R21") (pin "1") (pinfunction "1_1") (pintype "passive"))
    )
    (net (code "67") (name "Net-(R16-Pad1)") (class "Default")
      (node (ref "R16") (pin "1") (pinfunction "1_1") (pintype "passive"))
      (node (ref "R3") (pin "1") (pinfunction "1_1") (pintype "passive"))
      (node (ref "R9") (pin "2") (pinfunction "2_2") (pintype "passive"))
    )
    (net (code "68") (name "Net-(R56-Pad1)") (class "Default")
      (node (ref "R56") (pin "1") (pinfunction "1_1") (pintype "passive"))
      (node (ref "R60") (pin "2") (pinfunction "2_2") (pintype "passive"))
      (node (ref "R63") (pin "1") (pinfunction "1_1") (pintype "passive"))
    )
    (net (code "69") (name "Net-(R57-Pad1)") (class "Default")
      (node (ref "R57") (pin "1") (pinfunction "1_1") (pintype "passive"))
      (node (ref "R61") (pin "2") (pinfunction "2_2") (pintype "passive"))
      (node (ref "R64") (pin "1") (pinfunction "1_1") (pintype "passive"))
    )
    (net (code "70") (name "Net-(U1-1IN-)") (class "Default")
      (node (ref "R16") (pin "2") (pinfunction "2_2") (pintype "passive"))
      (node (ref "R18") (pin "2") (pinfunction "2_2") (pintype "passive"))
      (node (ref "U1") (pin "2") (pinfunction "1IN-_2") (pintype "input"))
    )
    (net (code "71") (name "Net-(U1-1OUT)") (class "Default")
      (node (ref "R18") (pin "1") (pinfunction "1_1") (pintype "passive"))
      (node (ref "R32") (pin "1") (pinfunction "1_1") (pintype "passive"))
      (node (ref "U1") (pin "1") (pinfunction "1OUT_1") (pintype "output"))
    )
    (net (code "72") (name "Net-(U1-2IN+)") (class "Default")
      (node (ref "R30") (pin "2") (pinfunction "2_2") (pintype "passive"))
      (node (ref "U1") (pin "5") (pinfunction "2IN+_5") (pintype "input"))
    )
    (net (code "73") (name "Net-(U1-2IN-)") (class "Default")
      (node (ref "R27") (pin "2") (pinfunction "2_2") (pintype "passive"))
      (node (ref "R32") (pin "2") (pinfunction "2_2") (pintype "passive"))
      (node (ref "R37") (pin "2") (pinfunction "2_2") (pintype "passive"))
      (node (ref "U1") (pin "6") (pinfunction "2IN-_6") (pintype "input"))
    )
    (net (code "74") (name "Net-(U2-1IN-)") (class "Default")
      (node (ref "R17") (pin "2") (pinfunction "2_2") (pintype "passive"))
      (node (ref "R19") (pin "2") (pinfunction "2_2") (pintype "passive"))
      (node (ref "U2") (pin "2") (pinfunction "1IN-_2") (pintype "input"))
    )
    (net (code "75") (name "Net-(U2-1OUT)") (class "Default")
      (node (ref "R19") (pin "1") (pinfunction "1_1") (pintype "passive"))
      (node (ref "R33") (pin "1") (pinfunction "1_1") (pintype "passive"))
      (node (ref "U2") (pin "1") (pinfunction "1OUT_1") (pintype "output"))
    )
    (net (code "76") (name "Net-(U2-2IN+)") (class "Default")
      (node (ref "R31") (pin "2") (pinfunction "2_2") (pintype "passive"))
      (node (ref "U2") (pin "5") (pinfunction "2IN+_5") (pintype "input"))
    )
    (net (code "77") (name "Net-(U2-2IN-)") (class "Default")
      (node (ref "R28") (pin "2") (pinfunction "2_2") (pintype "passive"))
      (node (ref "R33") (pin "2") (pinfunction "2_2") (pintype "passive"))
      (node (ref "R38") (pin "2") (pinfunction "2_2") (pintype "passive"))
      (node (ref "U2") (pin "6") (pinfunction "2IN-_6") (pintype "input"))
    )
    (net (code "78") (name "Net-(U3-1IN-)") (class "Default")
      (node (ref "R11") (pin "2") (pinfunction "2_2") (pintype "passive"))
      (node (ref "R22") (pin "2") (pinfunction "2_2") (pintype "passive"))
      (node (ref "U3") (pin "2") (pinfunction "1IN-_2") (pintype "input"))
    )
    (net (code "79") (name "Net-(U3-1OUT)") (class "Default")
      (node (ref "R22") (pin "1") (pinfunction "1_1") (pintype "passive"))
      (node (ref "R36") (pin "1") (pinfunction "1_1") (pintype "passive"))
      (node (ref "U3") (pin "1") (pinfunction "1OUT_1") (pintype "output"))
    )
    (net (code "80") (name "Net-(U3-2IN+)") (class "Default")
      (node (ref "P3") (pin "3") (pinfunction "3_3") (pintype "passive"))
      (node (ref "R41") (pin "2") (pinfunction "2_2") (pintype "passive"))
      (node (ref "U3") (pin "5") (pinfunction "2IN+_5") (pintype "input"))
    )
    (net (code "81") (name "Net-(U3-2IN-)") (class "Default")
      (node (ref "R29") (pin "2") (pinfunction "2_2") (pintype "passive"))
      (node (ref "R36") (pin "2") (pinfunction "2_2") (pintype "passive"))
      (node (ref "U3") (pin "6") (pinfunction "2IN-_6") (pintype "input"))
    )
    (net (code "82") (name "Net-(U4-1IN-)") (class "Default")
      (node (ref "R20") (pin "2") (pinfunction "2_2") (pintype "passive"))
      (node (ref "R23") (pin "2") (pinfunction "2_2") (pintype "passive"))
      (node (ref "U4") (pin "2") (pinfunction "1IN-_2") (pintype "input"))
    )
    (net (code "83") (name "Net-(U4-1OUT)") (class "Default")
      (node (ref "R23") (pin "1") (pinfunction "1_1") (pintype "passive"))
      (node (ref "R34") (pin "1") (pinfunction "1_1") (pintype "passive"))
      (node (ref "U4") (pin "1") (pinfunction "1OUT_1") (pintype "output"))
    )
    (net (code "84") (name "Net-(U4-2IN-)") (class "Default")
      (node (ref "R34") (pin "2") (pinfunction "2_2") (pintype "passive"))
      (node (ref "R39") (pin "2") (pinfunction "2_2") (pintype "passive"))
      (node (ref "U4") (pin "6") (pinfunction "2IN-_6") (pintype "input"))
    )
    (net (code "85") (name "Net-(U4-2OUT)") (class "Default")
      (node (ref "R39") (pin "1") (pinfunction "1_1") (pintype "passive"))
      (node (ref "R46") (pin "1") (pinfunction "1_1") (pintype "passive"))
      (node (ref "U4") (pin "7") (pinfunction "2OUT_7") (pintype "output"))
    )
    (net (code "86") (name "Net-(U5-1IN-)") (class "Default")
      (node (ref "R21") (pin "2") (pinfunction "2_2") (pintype "passive"))
      (node (ref "R24") (pin "2") (pinfunction "2_2") (pintype "passive"))
      (node (ref "U5") (pin "2") (pinfunction "1IN-_2") (pintype "input"))
    )
    (net (code "87") (name "Net-(U5-1OUT)") (class "Default")
      (node (ref "R24") (pin "1") (pinfunction "1_1") (pintype "passive"))
      (node (ref "R35") (pin "1") (pinfunction "1_1") (pintype "passive"))
      (node (ref "U5") (pin "1") (pinfunction "1OUT_1") (pintype "output"))
    )
    (net (code "88") (name "Net-(U5-2IN-)") (class "Default")
      (node (ref "R35") (pin "2") (pinfunction "2_2") (pintype "passive"))
      (node (ref "R40") (pin "2") (pinfunction "2_2") (pintype "passive"))
      (node (ref "U5") (pin "6") (pinfunction "2IN-_6") (pintype "input"))
    )
    (net (code "89") (name "Net-(U5-2OUT)") (class "Default")
      (node (ref "R40") (pin "1") (pinfunction "1_1") (pintype "passive"))
      (node (ref "R47") (pin "1") (pinfunction "1_1") (pintype "passive"))
      (node (ref "U5") (pin "7") (pinfunction "2OUT_7") (pintype "output"))
    )
    (net (code "90") (name "Net-(U6-1IN+)") (class "Default")
      (node (ref "R48") (pin "2") (pinfunction "2_2") (pintype "passive"))
      (node (ref "R49") (pin "2") (pinfunction "2_2") (pintype "passive"))
      (node (ref "U6") (pin "3") (pinfunction "1IN+_3") (pintype "input"))
    )
    (net (code "91") (name "Net-(U6-1IN-)") (class "Default")
      (node (ref "R46") (pin "2") (pinfunction "2_2") (pintype "passive"))
      (node (ref "R54") (pin "1") (pinfunction "1_1") (pintype "passive"))
      (node (ref "U6") (pin "2") (pinfunction "1IN-_2") (pintype "input"))
    )
    (net (code "92") (name "Net-(U7-1IN+)") (class "Default")
      (node (ref "R50") (pin "2") (pinfunction "2_2") (pintype "passive"))
      (node (ref "R51") (pin "2") (pinfunction "2_2") (pintype "passive"))
      (node (ref "U7") (pin "3") (pinfunction "1IN+_3") (pintype "input"))
    )
    (net (code "93") (name "Net-(U7-1IN-)") (class "Default")
      (node (ref "R47") (pin "2") (pinfunction "2_2") (pintype "passive"))
      (node (ref "R55") (pin "1") (pinfunction "1_1") (pintype "passive"))
      (node (ref "U7") (pin "2") (pinfunction "1IN-_2") (pintype "input"))
    )
    (net (code "94") (name "Net-(U8-1IN-)") (class "Default")
      (node (ref "R63") (pin "2") (pinfunction "2_2") (pintype "passive"))
      (node (ref "R65") (pin "2") (pinfunction "2_2") (pintype "passive"))
      (node (ref "U8") (pin "2") (pinfunction "1IN-_2") (pintype "input"))
    )
    (net (code "95") (name "Net-(U8-1OUT)") (class "Default")
      (node (ref "R65") (pin "1") (pinfunction "1_1") (pintype "passive"))
      (node (ref "R73") (pin "1") (pinfunction "1_1") (pintype "passive"))
      (node (ref "U8") (pin "1") (pinfunction "1OUT_1") (pintype "output"))
    )
    (net (code "96") (name "Net-(U8-2IN+)") (class "Default")
      (node (ref "R71") (pin "2") (pinfunction "2_2") (pintype "passive"))
      (node (ref "U8") (pin "5") (pinfunction "2IN+_5") (pintype "input"))
    )
    (net (code "97") (name "Net-(U8-2IN-)") (class "Default")
      (node (ref "R68") (pin "2") (pinfunction "2_2") (pintype "passive"))
      (node (ref "R73") (pin "2") (pinfunction "2_2") (pintype "passive"))
      (node (ref "R76") (pin "2") (pinfunction "2_2") (pintype "passive"))
      (node (ref "U8") (pin "6") (pinfunction "2IN-_6") (pintype "input"))
    )
    (net (code "98") (name "Net-(U9-1IN-)") (class "Default")
      (node (ref "R64") (pin "2") (pinfunction "2_2") (pintype "passive"))
      (node (ref "R66") (pin "2") (pinfunction "2_2") (pintype "passive"))
      (node (ref "U9") (pin "2") (pinfunction "1IN-_2") (pintype "input"))
    )
    (net (code "99") (name "Net-(U9-1OUT)") (class "Default")
      (node (ref "R66") (pin "1") (pinfunction "1_1") (pintype "passive"))
      (node (ref "R74") (pin "1") (pinfunction "1_1") (pintype "passive"))
      (node (ref "U9") (pin "1") (pinfunction "1OUT_1") (pintype "output"))
    )
    (net (code "100") (name "Net-(U9-2IN+)") (class "Default")
      (node (ref "R72") (pin "2") (pinfunction "2_2") (pintype "passive"))
      (node (ref "U9") (pin "5") (pinfunction "2IN+_5") (pintype "input"))
    )
    (net (code "101") (name "Net-(U9-2IN-)") (class "Default")
      (node (ref "R69") (pin "2") (pinfunction "2_2") (pintype "passive"))
      (node (ref "R74") (pin "2") (pinfunction "2_2") (pintype "passive"))
      (node (ref "R77") (pin "2") (pinfunction "2_2") (pintype "passive"))
      (node (ref "U9") (pin "6") (pinfunction "2IN-_6") (pintype "input"))
    )
    (net (code "102") (name "Net-(U10-1IN-)") (class "Default")
      (node (ref "R62") (pin "2") (pinfunction "2_2") (pintype "passive"))
      (node (ref "R67") (pin "2") (pinfunction "2_2") (pintype "passive"))
      (node (ref "U10") (pin "2") (pinfunction "1IN-_2") (pintype "input"))
    )
    (net (code "103") (name "Net-(U10-1OUT)") (class "Default")
      (node (ref "R67") (pin "1") (pinfunction "1_1") (pintype "passive"))
      (node (ref "R75") (pin "1") (pinfunction "1_1") (pintype "passive"))
      (node (ref "U10") (pin "1") (pinfunction "1OUT_1") (pintype "output"))
    )
    (net (code "104") (name "Net-(U10-2IN+)") (class "Default")
      (node (ref "P8") (pin "3") (pinfunction "3_3") (pintype "passive"))
      (node (ref "R78") (pin "2") (pinfunction "2_2") (pintype "passive"))
      (node (ref "U10") (pin "5") (pinfunction "2IN+_5") (pintype "input"))
    )
    (net (code "105") (name "Net-(U10-2IN-)") (class "Default")
      (node (ref "R70") (pin "2") (pinfunction "2_2") (pintype "passive"))
      (node (ref "R75") (pin "2") (pinfunction "2_2") (pintype "passive"))
      (node (ref "U10") (pin "6") (pinfunction "2IN-_6") (pintype "input"))
    )
    (net (code "106") (name "Net-(U14-Cap+)") (class "Default")
      (node (ref "C7") (pin "2") (pinfunction "2_2") (pintype "passive"))
      (node (ref "U14") (pin "2") (pinfunction "Cap+_2") (pintype "input"))
    )
    (net (code "107") (name "Net-(U14-Cap-)") (class "Default")
      (node (ref "C7") (pin "1") (pinfunction "1_1") (pintype "passive"))
      (node (ref "U14") (pin "4") (pinfunction "Cap-_4") (pintype "power_in"))
    )
    (net (code "108") (name "Net-(U15-Cap+)") (class "Default")
      (node (ref "C8") (pin "2") (pinfunction "2_2") (pintype "passive"))
      (node (ref "U15") (pin "2") (pinfunction "Cap+_2") (pintype "input"))
    )
    (net (code "109") (name "Net-(U15-Cap-)") (class "Default")
      (node (ref "C8") (pin "1") (pinfunction "1_1") (pintype "passive"))
      (node (ref "U15") (pin "4") (pinfunction "Cap-_4") (pintype "power_in"))
    )
    (net (code "110") (name "Net-(U16-Cap+)") (class "Default")
      (node (ref "C9") (pin "2") (pinfunction "2_2") (pintype "passive"))
      (node (ref "U16") (pin "2") (pinfunction "Cap+_2") (pintype "input"))
    )
    (net (code "111") (name "Net-(U16-Cap-)") (class "Default")
      (node (ref "C9") (pin "1") (pinfunction "1_1") (pintype "passive"))
      (node (ref "U16") (pin "4") (pinfunction "Cap-_4") (pintype "power_in"))
    )
    (net (code "112") (name "unconnected-(P1-Pad1)") (class "Default")
      (node (ref "P1") (pin "1") (pinfunction "1_1") (pintype "passive+no_connect"))
    )
    (net (code "113") (name "unconnected-(P2-Pad1)") (class "Default")
      (node (ref "P2") (pin "1") (pinfunction "1_1") (pintype "passive+no_connect"))
    )
    (net (code "114") (name "unconnected-(P3-Pad1)") (class "Default")
      (node (ref "P3") (pin "1") (pinfunction "1_1") (pintype "passive+no_connect"))
    )
    (net (code "115") (name "unconnected-(P4-Pad3)") (class "Default")
      (node (ref "P4") (pin "3") (pinfunction "3_3") (pintype "passive+no_connect"))
    )
    (net (code "116") (name "unconnected-(P5-Pad3)") (class "Default")
      (node (ref "P5") (pin "3") (pinfunction "3_3") (pintype "passive+no_connect"))
    )
    (net (code "117") (name "unconnected-(P6-Pad1)") (class "Default")
      (node (ref "P6") (pin "1") (pinfunction "1_1") (pintype "passive+no_connect"))
    )
    (net (code "118") (name "unconnected-(P7-Pad1)") (class "Default")
      (node (ref "P7") (pin "1") (pinfunction "1_1") (pintype "passive+no_connect"))
    )
    (net (code "119") (name "unconnected-(P8-Pad1)") (class "Default")
      (node (ref "P8") (pin "1") (pinfunction "1_1") (pintype "passive+no_connect"))
    )
    (net (code "120") (name "unconnected-(U6-2IN+-Pad5)") (class "Default")
      (node (ref "U6") (pin "5") (pinfunction "2IN+_5") (pintype "input+no_connect"))
    )
    (net (code "121") (name "unconnected-(U6-2IN--Pad6)") (class "Default")
      (node (ref "U6") (pin "6") (pinfunction "2IN-_6") (pintype "input+no_connect"))
    )
    (net (code "122") (name "unconnected-(U6-2OUT-Pad7)") (class "Default")
      (node (ref "U6") (pin "7") (pinfunction "2OUT_7") (pintype "output+no_connect"))
    )
    (net (code "123") (name "unconnected-(U7-2IN+-Pad5)") (class "Default")
      (node (ref "U7") (pin "5") (pinfunction "2IN+_5") (pintype "input+no_connect"))
    )
    (net (code "124") (name "unconnected-(U7-2IN--Pad6)") (class "Default")
      (node (ref "U7") (pin "6") (pinfunction "2IN-_6") (pintype "input+no_connect"))
    )
    (net (code "125") (name "unconnected-(U7-2OUT-Pad7)") (class "Default")
      (node (ref "U7") (pin "7") (pinfunction "2OUT_7") (pintype "output+no_connect"))
    )
    (net (code "126") (name "unconnected-(U11-EN-Pad4)") (class "Default")
      (node (ref "U11") (pin "4") (pinfunction "EN_4") (pintype "passive+no_connect"))
    )
    (net (code "127") (name "unconnected-(U12-EN-Pad3)") (class "Default")
      (node (ref "U12") (pin "3") (pinfunction "EN_3") (pintype "passive"))
    )
    (net (code "128") (name "unconnected-(U12-R+-Pad4)") (class "Default")
      (node (ref "U12") (pin "4") (pinfunction "R+_4") (pintype "passive"))
    )
    (net (code "129") (name "unconnected-(U12-R--Pad5)") (class "Default")
      (node (ref "U12") (pin "5") (pinfunction "R-_5") (pintype "passive"))
    )
    (net (code "130") (name "unconnected-(U12-V3-Pad8)") (class "Default")
      (node (ref "U12") (pin "8") (pinfunction "V3_8") (pintype "passive+no_connect"))
    )
    (net (code "131") (name "unconnected-(U13-EN-Pad4)") (class "Default")
      (node (ref "U13") (pin "4") (pinfunction "EN_4") (pintype "passive+no_connect"))
    )
    (net (code "132") (name "unconnected-(U14-FB{slash}SHDN-Pad1)") (class "Default")
      (node (ref "U14") (pin "1") (pinfunction "FB/SHDN_1") (pintype "output+no_connect"))
    )
    (net (code "133") (name "unconnected-(U14-LV(Vref)-Pad6)") (class "Default")
      (node (ref "U14") (pin "6") (pinfunction "LV(Vref)_6") (pintype "input+no_connect"))
    )
    (net (code "134") (name "unconnected-(U14-OSC-Pad7)") (class "Default")
      (node (ref "U14") (pin "7") (pinfunction "OSC_7") (pintype "output+no_connect"))
    )
    (net (code "135") (name "unconnected-(U15-FB{slash}SHDN-Pad1)") (class "Default")
      (node (ref "U15") (pin "1") (pinfunction "FB/SHDN_1") (pintype "output+no_connect"))
    )
    (net (code "136") (name "unconnected-(U15-LV(Vref)-Pad6)") (class "Default")
      (node (ref "U15") (pin "6") (pinfunction "LV(Vref)_6") (pintype "input+no_connect"))
    )
    (net (code "137") (name "unconnected-(U15-OSC-Pad7)") (class "Default")
      (node (ref "U15") (pin "7") (pinfunction "OSC_7") (pintype "output+no_connect"))
    )
    (net (code "138") (name "unconnected-(U16-FB{slash}SHDN-Pad1)") (class "Default")
      (node (ref "U16") (pin "1") (pinfunction "FB/SHDN_1") (pintype "output+no_connect"))
    )
    (net (code "139") (name "unconnected-(U16-LV(Vref)-Pad6)") (class "Default")
      (node (ref "U16") (pin "6") (pinfunction "LV(Vref)_6") (pintype "input+no_connect"))
    )
    (net (code "140") (name "unconnected-(U16-OSC-Pad7)") (class "Default")
      (node (ref "U16") (pin "7") (pinfunction "OSC_7") (pintype "output+no_connect"))
    )
  )
)
